# 5_spi_memory.net
KiCad netlist of a schematic drawn in Altium Designer
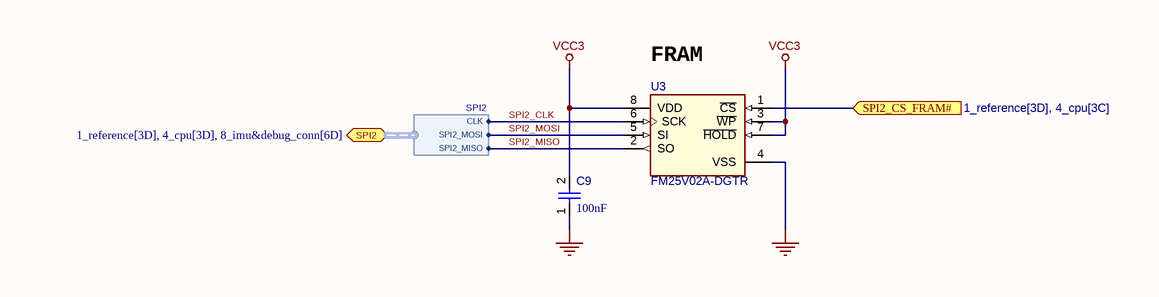
[diagram p0: 5_spi_memory.SchDoc]

(export (version "E")
  (design (tool "Eeschema 10.0.6"))
  (components
    (comp (ref "C9")
      (value "100nF")
      (footprint "CAPC0402(1005)60_L")
      (description "Chip Capacitor, 100nF +/-20%, 10V, 0402, Thickness 0.6 mm")
      (fields (field (name "TOLERANCE") "20%") (field (name "Comment") "Capacitor 100nF +/-20% 10V 0402"))
      (libsource (lib "MHH -  Altium Advanced Course A365 01") (part "CAP-NP-2"))
    )
    (comp (ref "U3")
      (value "FM25V02A-DGTR")
      (footprint "SON95P400X75_HS-9N")
      (description "REEL / F-RAM Memory Serial")
      (libsource (lib "MHH -  Altium Advanced Course A365 01") (part "CMP-019-00000-4"))
    )
  )
  (nets
    (net (code "2") (name "/SPI2_CLK") (class "Default")
      (node (ref "U3") (pin "6") (pinfunction "SCK_6") (pintype "input"))
    )
    (net (code "3") (name "/SPI2_CS_FRAM#") (class "Default")
      (node (ref "U3") (pin "1") (pinfunction "~{CS}_1") (pintype "input"))
    )
    (net (code "4") (name "/SPI2_MISO") (class "Default")
      (node (ref "U3") (pin "2") (pinfunction "SO_2") (pintype "output"))
    )
    (net (code "5") (name "/SPI2_MOSI") (class "Default")
      (node (ref "U3") (pin "5") (pinfunction "SI_5") (pintype "input"))
    )
    (net (code "7") (name "GND") (class "Default")
      (node (ref "C9") (pin "1") (pinfunction "1_1") (pintype "passive"))
      (node (ref "U3") (pin "4") (pinfunction "VSS_4") (pintype "power_in"))
    )
    (net (code "8") (name "VCC3") (class "Default")
      (node (ref "C9") (pin "2") (pinfunction "2_2") (pintype "passive"))
      (node (ref "U3") (pin "3") (pinfunction "~{WP}_3") (pintype "input"))
      (node (ref "U3") (pin "7") (pinfunction "~{HOLD}_7") (pintype "input"))
      (node (ref "U3") (pin "8") (pinfunction "VDD_8") (pintype "power_in"))
    )
  )
)
